# Speaker_Driver.net
KiCad netlist of a schematic drawn in Altium Designer
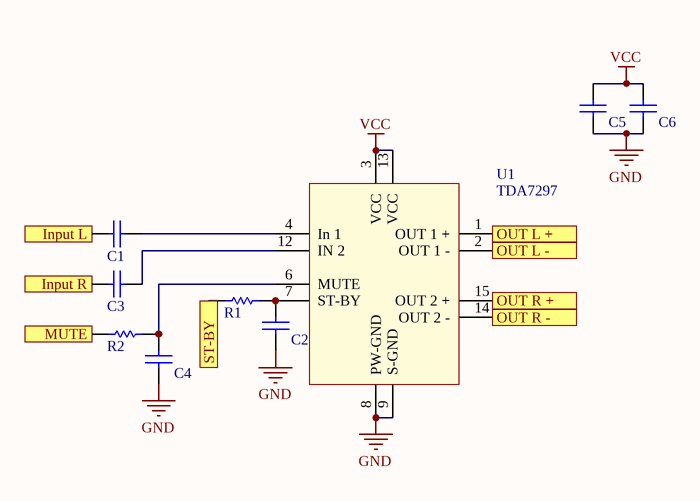
[diagram p0: Speaker Driver.SchDoc]

(export (version "E")
  (design (tool "Eeschema 10.0.6"))
  (components
    (comp (ref "C1")
      (value "1206GC102KAT1A")
      (footprint "AVX-1206-2_L")
      (description "Chip Capacitor, 1 nF, +/- 10%, -55 to 125 degC, 1206 (3216 Metric), RoHS, Tape and Reel")
      (fields (field (name "TOLERANCE") "10%") (field (name "MANUFACTURER") "AVX"))
      (libsource (lib "Altium Content Vault") (part "CAP-NP-2"))
    )
    (comp (ref "C2")
      (value "1206GC102KAT1A")
      (footprint "AVX-1206-2_L")
      (description "Chip Capacitor, 1 nF, +/- 10%, -55 to 125 degC, 1206 (3216 Metric), RoHS, Tape and Reel")
      (fields (field (name "TOLERANCE") "10%") (field (name "MANUFACTURER") "AVX"))
      (libsource (lib "Altium Content Vault") (part "CAP-NP-2"))
    )
    (comp (ref "C3")
      (value "1206GC102KAT1A")
      (footprint "AVX-1206-2_L")
      (description "Chip Capacitor, 1 nF, +/- 10%, -55 to 125 degC, 1206 (3216 Metric), RoHS, Tape and Reel")
      (fields (field (name "TOLERANCE") "10%") (field (name "MANUFACTURER") "AVX"))
      (libsource (lib "Altium Content Vault") (part "CAP-NP-2"))
    )
    (comp (ref "C4")
      (value "1206GC102KAT1A")
      (footprint "AVX-1206-2_L")
      (description "Chip Capacitor, 1 nF, +/- 10%, -55 to 125 degC, 1206 (3216 Metric), RoHS, Tape and Reel")
      (fields (field (name "TOLERANCE") "10%") (field (name "MANUFACTURER") "AVX"))
      (libsource (lib "Altium Content Vault") (part "CAP-NP-2"))
    )
    (comp (ref "C5")
      (value "1206GC102KAT1A")
      (footprint "AVX-1206-2_L")
      (description "Chip Capacitor, 1 nF, +/- 10%, -55 to 125 degC, 1206 (3216 Metric), RoHS, Tape and Reel")
      (fields (field (name "TOLERANCE") "10%") (field (name "MANUFACTURER") "AVX"))
      (libsource (lib "Altium Content Vault") (part "CAP-NP-2"))
    )
    (comp (ref "C6")
      (value "1206GC102KAT1A")
      (footprint "AVX-1206-2_L")
      (description "Chip Capacitor, 1 nF, +/- 10%, -55 to 125 degC, 1206 (3216 Metric), RoHS, Tape and Reel")
      (fields (field (name "TOLERANCE") "10%") (field (name "MANUFACTURER") "AVX"))
      (libsource (lib "Altium Content Vault") (part "CAP-NP-2"))
    )
    (comp (ref "R1")
      (value "ERJ-8GEY0R00V")
      (footprint "RESC3216X70X50NL05T20")
      (fields (field (name "MANUFACTURER") "Panasonic"))
      (libsource (lib "Altium Content Vault") (part "RES"))
    )
    (comp (ref "R2")
      (value "ERJ-8GEY0R00V")
      (footprint "RESC3216X70X50NL05T20")
      (fields (field (name "MANUFACTURER") "Panasonic"))
      (libsource (lib "Altium Content Vault") (part "RES"))
    )
    (comp (ref "U1") (value "TDA7297") (footprint "TDA7297") (libsource (lib "Schlib") (part "TDA7297")))
  )
  (nets
    (net (code "1") (name "/Input L") (class "Default")
      (node (ref "C1") (pin "2") (pinfunction "2_2") (pintype "passive"))
    )
    (net (code "2") (name "/Input R") (class "Default")
      (node (ref "C3") (pin "2") (pinfunction "2_2") (pintype "passive"))
    )
    (net (code "3") (name "/MUTE") (class "Default")
      (node (ref "R2") (pin "1") (pinfunction "1_1") (pintype "passive"))
    )
    (net (code "4") (name "/OUT L +") (class "Default")
      (node (ref "U1") (pin "1") (pinfunction "OUT_1_+_1") (pintype "passive"))
    )
    (net (code "5") (name "/OUT L -") (class "Default")
      (node (ref "U1") (pin "2") (pinfunction "OUT_1_-_2") (pintype "passive"))
    )
    (net (code "6") (name "/OUT R +") (class "Default")
      (node (ref "U1") (pin "15") (pinfunction "OUT_2_+_15") (pintype "passive"))
    )
    (net (code "7") (name "/OUT R -") (class "Default")
      (node (ref "U1") (pin "14") (pinfunction "OUT_2_-_14") (pintype "passive"))
    )
    (net (code "8") (name "/ST-BY") (class "Default")
      (node (ref "R1") (pin "1") (pinfunction "1_1") (pintype "passive"))
    )
    (net (code "9") (name "GND") (class "Default")
      (node (ref "C2") (pin "2") (pinfunction "2_2") (pintype "passive"))
      (node (ref "C4") (pin "2") (pinfunction "2_2") (pintype "passive"))
      (node (ref "C5") (pin "2") (pinfunction "2_2") (pintype "passive"))
      (node (ref "C6") (pin "2") (pinfunction "2_2") (pintype "passive"))
      (node (ref "U1") (pin "8") (pinfunction "PW-GND_8") (pintype "passive"))
      (node (ref "U1") (pin "9") (pinfunction "S-GND_9") (pintype "passive"))
    )
    (net (code "10") (name "Net-(U1-IN_2)") (class "Default")
      (node (ref "C3") (pin "1") (pinfunction "1_1") (pintype "passive"))
      (node (ref "U1") (pin "12") (pinfunction "IN_2_12") (pintype "passive"))
    )
    (net (code "11") (name "Net-(U1-In_1)") (class "Default")
      (node (ref "C1") (pin "1") (pinfunction "1_1") (pintype "passive"))
      (node (ref "U1") (pin "4") (pinfunction "In_1_4") (pintype "passive"))
    )
    (net (code "12") (name "Net-(U1-MUTE)") (class "Default")
      (node (ref "C4") (pin "1") (pinfunction "1_1") (pintype "passive"))
      (node (ref "R2") (pin "2") (pinfunction "2_2") (pintype "passive"))
      (node (ref "U1") (pin "6") (pinfunction "MUTE_6") (pintype "passive"))
    )
    (net (code "13") (name "Net-(U1-ST-BY)") (class "Default")
      (node (ref "C2") (pin "1") (pinfunction "1_1") (pintype "passive"))
      (node (ref "R1") (pin "2") (pinfunction "2_2") (pintype "passive"))
      (node (ref "U1") (pin "7") (pinfunction "ST-BY_7") (pintype "passive"))
    )
    (net (code "14") (name "VCC") (class "Default")
      (node (ref "C5") (pin "1") (pinfunction "1_1") (pintype "passive"))
      (node (ref "C6") (pin "1") (pinfunction "1_1") (pintype "passive"))
      (node (ref "U1") (pin "13") (pinfunction "VCC_13") (pintype "passive"))
      (node (ref "U1") (pin "3") (pinfunction "VCC_3") (pintype "passive"))
    )
  )
)
